# spider_mx8_2side_serial.net
KiCad netlist of a schematic drawn in EAGLE
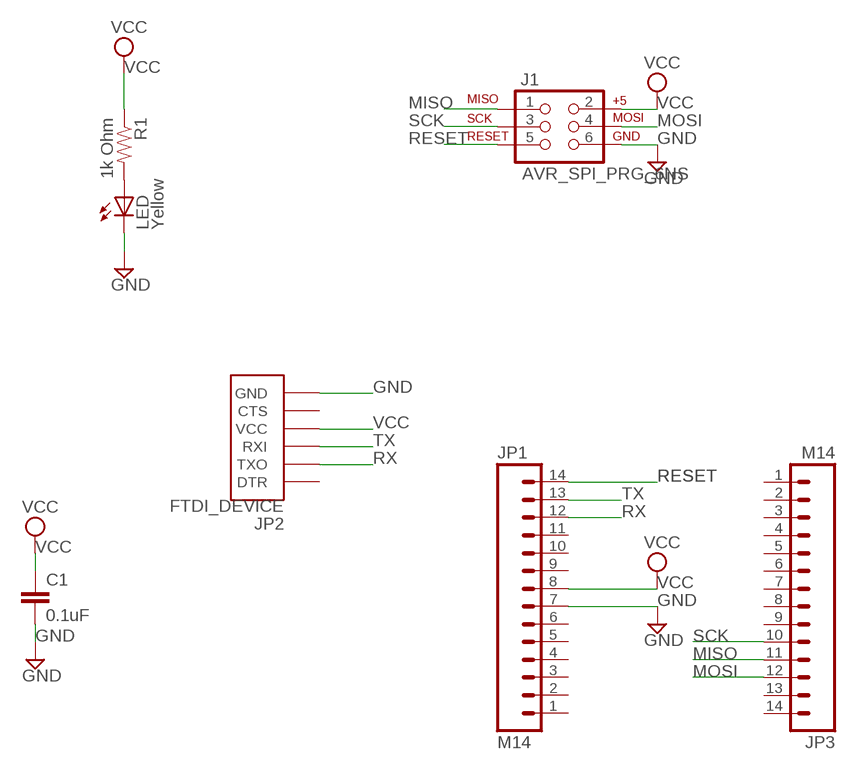
[diagram p0: schematic, sheet 1]

(export (version "E")
  (design (tool "Eeschema 10.0.6"))
  (components
    (comp (ref "C1")
      (value "0.1uF")
      (footprint "eagle-import:1206")
      (libsource (lib "eagle-import") (part "CAP1206"))
    )
    (comp (ref "J1")
      (value "AVR_SPI_PRG_6NS")
      (footprint "eagle-import:2X3-NS")
      (libsource (lib "eagle-import") (part "AVR_SPI_PRG_6NS"))
    )
    (comp (ref "JP1")
      (value "M14")
      (footprint "eagle-import:1X14")
      (libsource (lib "eagle-import") (part "M14"))
    )
    (comp (ref "JP2")
      (value "FTDI_DEVICE")
      (footprint "eagle-import:FTDI_DEVICE_SIDE")
      (libsource (lib "eagle-import") (part "FTDI_DEVICE"))
    )
    (comp (ref "JP3")
      (value "M14")
      (footprint "eagle-import:1X14")
      (libsource (lib "eagle-import") (part "M14"))
    )
    (comp (ref "LED")
      (value "Yellow")
      (footprint "eagle-import:LED-1206")
      (libsource (lib "eagle-import") (part "LED-YELLOWLILYPAD"))
    )
    (comp (ref "R1")
      (value "1k Ohm")
      (footprint "eagle-import:1206")
      (libsource (lib "eagle-import") (part "RESISTOR1206"))
    )
  )
  (nets
    (net (code "1") (name "/MISO") (class "Default")
      (node (ref "J1") (pin "1") (pinfunction "1_1") (pintype "passive"))
      (node (ref "JP3") (pin "11") (pinfunction "11_11") (pintype "passive"))
    )
    (net (code "2") (name "/MOSI") (class "Default")
      (node (ref "J1") (pin "4") (pinfunction "4_4") (pintype "passive"))
      (node (ref "JP3") (pin "12") (pinfunction "12_12") (pintype "passive"))
    )
    (net (code "3") (name "/RESET") (class "Default")
      (node (ref "J1") (pin "5") (pinfunction "5_5") (pintype "passive"))
      (node (ref "JP1") (pin "14") (pinfunction "14_14") (pintype "passive"))
    )
    (net (code "4") (name "/RX") (class "Default")
      (node (ref "JP1") (pin "12") (pinfunction "12_12") (pintype "passive"))
      (node (ref "JP2") (pin "P$2") (pinfunction "TXO_P$2") (pintype "bidirectional"))
    )
    (net (code "5") (name "/SCK") (class "Default")
      (node (ref "J1") (pin "3") (pinfunction "3_3") (pintype "passive"))
      (node (ref "JP3") (pin "10") (pinfunction "10_10") (pintype "passive"))
    )
    (net (code "6") (name "/TX") (class "Default")
      (node (ref "JP1") (pin "13") (pinfunction "13_13") (pintype "passive"))
      (node (ref "JP2") (pin "P$3") (pinfunction "RXI_P$3") (pintype "bidirectional"))
    )
    (net (code "7") (name "GND") (class "Default")
      (node (ref "C1") (pin "2") (pinfunction "2_2") (pintype "passive"))
      (node (ref "J1") (pin "6") (pinfunction "6_6") (pintype "passive"))
      (node (ref "JP1") (pin "7") (pinfunction "7_7") (pintype "passive"))
      (node (ref "JP2") (pin "P$6") (pinfunction "GND_P$6") (pintype "bidirectional"))
      (node (ref "LED") (pin "C") (pinfunction "C_C") (pintype "passive"))
    )
    (net (code "8") (name "Net-(LED-PadA)") (class "Default")
      (node (ref "LED") (pin "A") (pinfunction "A_A") (pintype "passive"))
      (node (ref "R1") (pin "2") (pinfunction "2_2") (pintype "passive"))
    )
    (net (code "9") (name "VCC") (class "Default")
      (node (ref "C1") (pin "1") (pinfunction "1_1") (pintype "passive"))
      (node (ref "J1") (pin "2") (pinfunction "2_2") (pintype "passive"))
      (node (ref "JP1") (pin "8") (pinfunction "8_8") (pintype "passive"))
      (node (ref "JP2") (pin "P$4") (pinfunction "VCC_P$4") (pintype "bidirectional"))
      (node (ref "R1") (pin "1") (pinfunction "1_1") (pintype "passive"))
    )
    (net (code "10") (name "unconnected-(JP1-Pad1)") (class "Default")
      (node (ref "JP1") (pin "1") (pinfunction "1_1") (pintype "passive"))
    )
    (net (code "11") (name "unconnected-(JP1-Pad2)") (class "Default")
      (node (ref "JP1") (pin "2") (pinfunction "2_2") (pintype "passive"))
    )
    (net (code "12") (name "unconnected-(JP1-Pad3)") (class "Default")
      (node (ref "JP1") (pin "3") (pinfunction "3_3") (pintype "passive"))
    )
    (net (code "13") (name "unconnected-(JP1-Pad4)") (class "Default")
      (node (ref "JP1") (pin "4") (pinfunction "4_4") (pintype "passive"))
    )
    (net (code "14") (name "unconnected-(JP1-Pad5)") (class "Default")
      (node (ref "JP1") (pin "5") (pinfunction "5_5") (pintype "passive"))
    )
    (net (code "15") (name "unconnected-(JP1-Pad6)") (class "Default")
      (node (ref "JP1") (pin "6") (pinfunction "6_6") (pintype "passive"))
    )
    (net (code "16") (name "unconnected-(JP1-Pad9)") (class "Default")
      (node (ref "JP1") (pin "9") (pinfunction "9_9") (pintype "passive"))
    )
    (net (code "17") (name "unconnected-(JP1-Pad10)") (class "Default")
      (node (ref "JP1") (pin "10") (pinfunction "10_10") (pintype "passive"))
    )
    (net (code "18") (name "unconnected-(JP1-Pad11)") (class "Default")
      (node (ref "JP1") (pin "11") (pinfunction "11_11") (pintype "passive"))
    )
    (net (code "19") (name "unconnected-(JP2-CTS-PadP$5)") (class "Default")
      (node (ref "JP2") (pin "P$5") (pinfunction "CTS_P$5") (pintype "bidirectional"))
    )
    (net (code "20") (name "unconnected-(JP2-DTR-PadP$1)") (class "Default")
      (node (ref "JP2") (pin "P$1") (pinfunction "DTR_P$1") (pintype "bidirectional"))
    )
    (net (code "21") (name "unconnected-(JP3-Pad1)") (class "Default")
      (node (ref "JP3") (pin "1") (pinfunction "1_1") (pintype "passive"))
    )
    (net (code "22") (name "unconnected-(JP3-Pad2)") (class "Default")
      (node (ref "JP3") (pin "2") (pinfunction "2_2") (pintype "passive"))
    )
    (net (code "23") (name "unconnected-(JP3-Pad3)") (class "Default")
      (node (ref "JP3") (pin "3") (pinfunction "3_3") (pintype "passive"))
    )
    (net (code "24") (name "unconnected-(JP3-Pad4)") (class "Default")
      (node (ref "JP3") (pin "4") (pinfunction "4_4") (pintype "passive"))
    )
    (net (code "25") (name "unconnected-(JP3-Pad5)") (class "Default")
      (node (ref "JP3") (pin "5") (pinfunction "5_5") (pintype "passive"))
    )
    (net (code "26") (name "unconnected-(JP3-Pad6)") (class "Default")
      (node (ref "JP3") (pin "6") (pinfunction "6_6") (pintype "passive"))
    )
    (net (code "27") (name "unconnected-(JP3-Pad7)") (class "Default")
      (node (ref "JP3") (pin "7") (pinfunction "7_7") (pintype "passive"))
    )
    (net (code "28") (name "unconnected-(JP3-Pad8)") (class "Default")
      (node (ref "JP3") (pin "8") (pinfunction "8_8") (pintype "passive"))
    )
    (net (code "29") (name "unconnected-(JP3-Pad9)") (class "Default")
      (node (ref "JP3") (pin "9") (pinfunction "9_9") (pintype "passive"))
    )
    (net (code "30") (name "unconnected-(JP3-Pad13)") (class "Default")
      (node (ref "JP3") (pin "13") (pinfunction "13_13") (pintype "passive"))
    )
    (net (code "31") (name "unconnected-(JP3-Pad14)") (class "Default")
      (node (ref "JP3") (pin "14") (pinfunction "14_14") (pintype "passive"))
    )
  )
)
